# AD4DA-LightUI.net
KiCad netlist of a schematic drawn in EAGLE
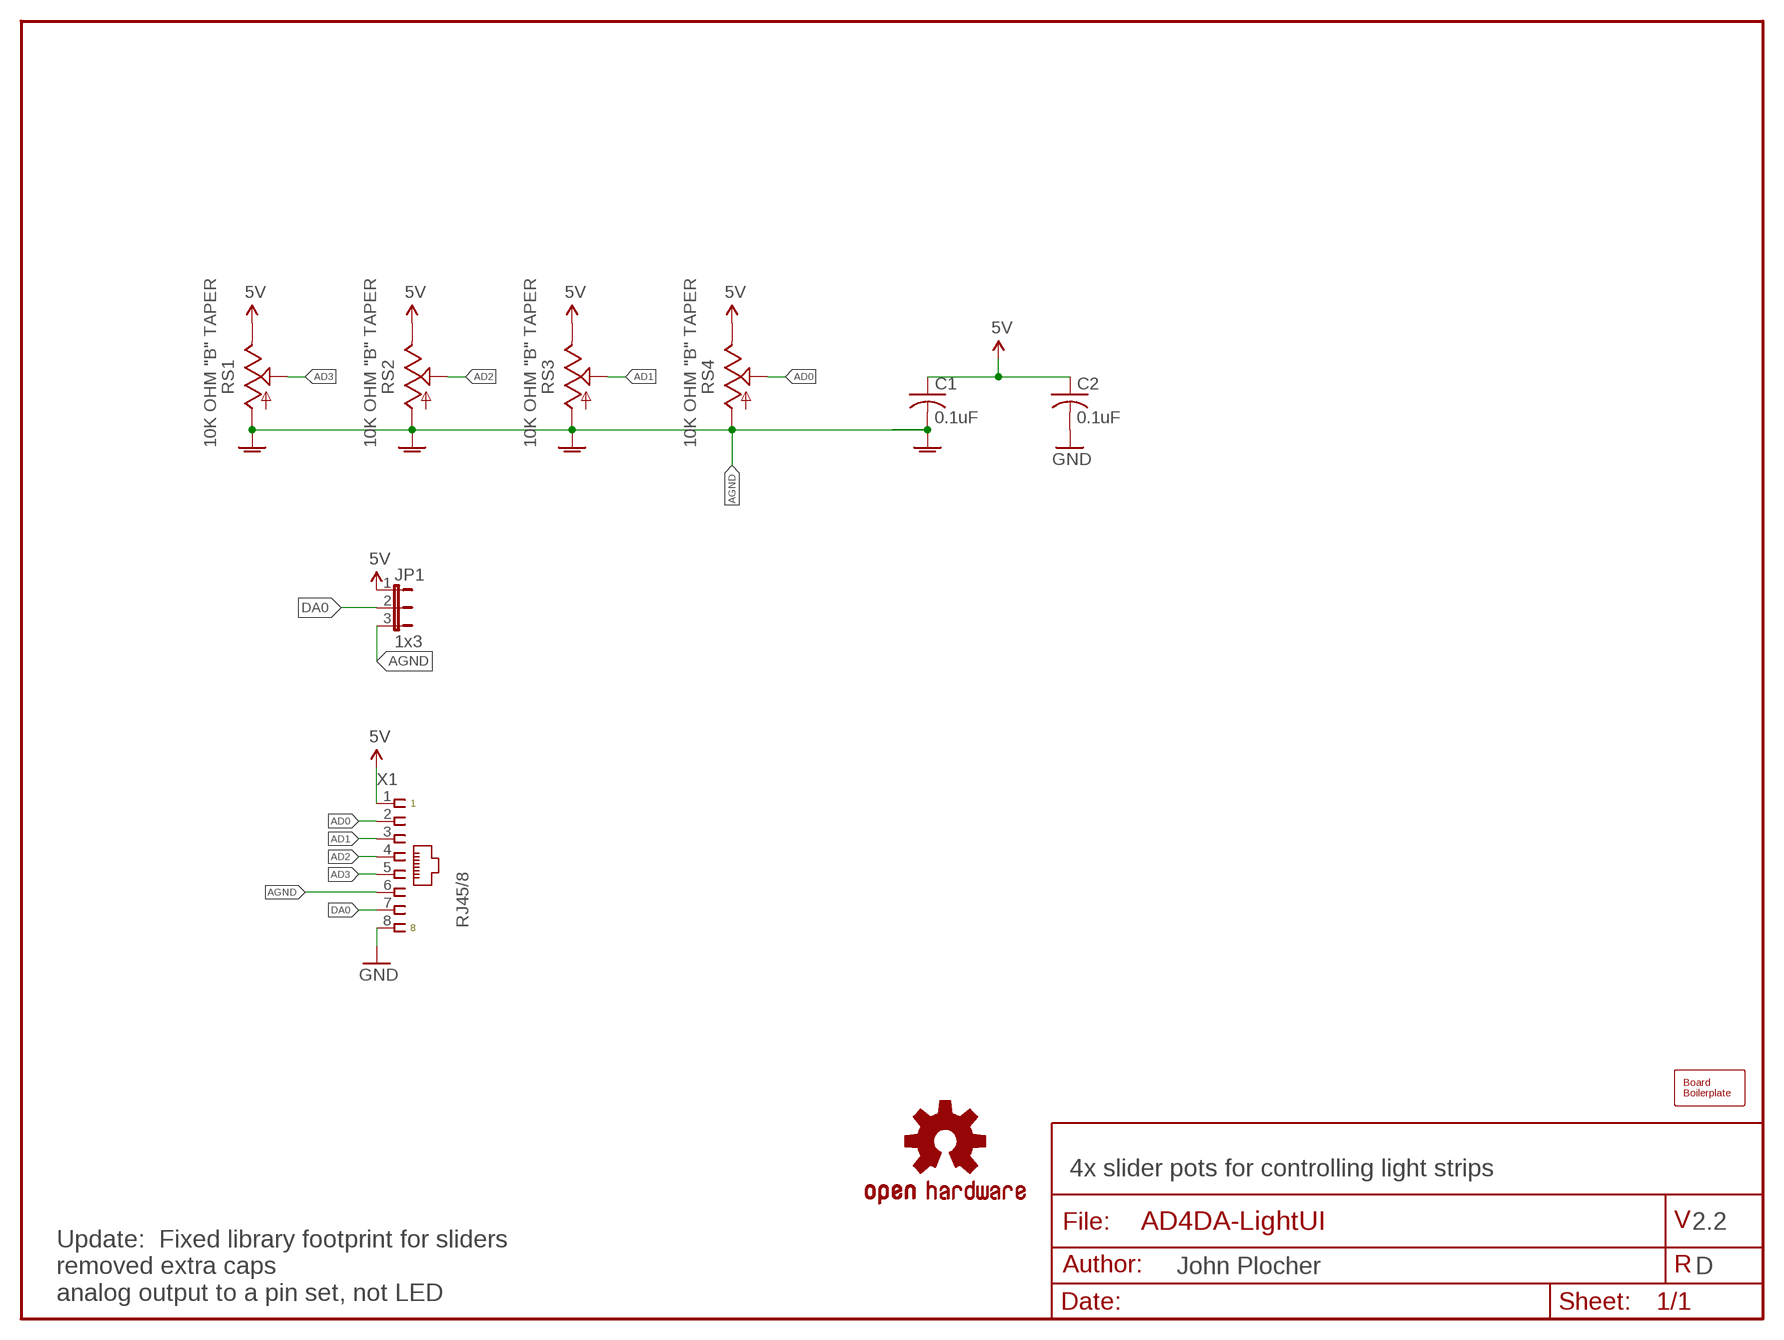
[diagram p0: schematic, sheet 1]

(export (version "E")
  (design (tool "Eeschema 10.0.6"))
  (components
    (comp (ref "BOARD1")
      (value "10x7cm")
      (footprint "eagle-import:BOARD-DINRAIL-3.17INX7CM")
      (libsource (lib "eagle-import") (part "BOARD80X70"))
    )
    (comp (ref "C1")
      (value "0.1uF")
      (footprint "eagle-import:C050-024X044")
      (libsource (lib "eagle-import") (part "CAPPTH1"))
    )
    (comp (ref "C2")
      (value "0.1uF")
      (footprint "eagle-import:C050-024X044")
      (libsource (lib "eagle-import") (part "CAPPTH1"))
    )
    (comp (ref "JP1")
      (value "1x3")
      (footprint "eagle-import:1X03")
      (libsource (lib "eagle-import") (part "JUMPER-3PTH-LOCK"))
    )
    (comp (ref "LOGO1")
      (value "DOC-OSHW-LOGO-L")
      (footprint "eagle-import:OSHW-LOGO-L")
      (libsource (lib "eagle-import") (part "DOC-OSHW-LOGO-L"))
    )
    (comp (ref "RS1")
      (value "10K OHM \"B\" TAPER")
      (footprint "eagle-import:SLIDER-45MM")
      (libsource (lib "eagle-import") (part "R-SLIDE-POT-45MM"))
    )
    (comp (ref "RS2")
      (value "10K OHM \"B\" TAPER")
      (footprint "eagle-import:SLIDER-45MM")
      (libsource (lib "eagle-import") (part "R-SLIDE-POT-45MM"))
    )
    (comp (ref "RS3")
      (value "10K OHM \"B\" TAPER")
      (footprint "eagle-import:SLIDER-45MM")
      (libsource (lib "eagle-import") (part "R-SLIDE-POT-45MM"))
    )
    (comp (ref "RS4")
      (value "10K OHM \"B\" TAPER")
      (footprint "eagle-import:SLIDER-45MM")
      (libsource (lib "eagle-import") (part "R-SLIDE-POT-45MM"))
    )
    (comp (ref "X1")
      (value "RJ45/8")
      (footprint "eagle-import:RJ45-NO-SHIELD")
      (libsource (lib "eagle-import") (part "CONNECTOR-RJ45-FRONT"))
    )
  )
  (nets
    (net (code "1") (name "5V") (class "Default")
      (node (ref "C1") (pin "1") (pinfunction "1_1") (pintype "passive"))
      (node (ref "C2") (pin "1") (pinfunction "1_1") (pintype "passive"))
      (node (ref "JP1") (pin "1") (pinfunction "1_1") (pintype "passive"))
      (node (ref "RS1") (pin "E") (pinfunction "E_E") (pintype "passive"))
      (node (ref "RS2") (pin "E") (pinfunction "E_E") (pintype "passive"))
      (node (ref "RS3") (pin "E") (pinfunction "E_E") (pintype "passive"))
      (node (ref "RS4") (pin "E") (pinfunction "E_E") (pintype "passive"))
      (node (ref "X1") (pin "1") (pinfunction "1_1") (pintype "passive"))
    )
    (net (code "2") (name "AD0") (class "Default")
      (node (ref "RS4") (pin "S") (pinfunction "S_S") (pintype "passive"))
      (node (ref "X1") (pin "2") (pinfunction "2_2") (pintype "passive"))
    )
    (net (code "3") (name "AD1") (class "Default")
      (node (ref "RS3") (pin "S") (pinfunction "S_S") (pintype "passive"))
      (node (ref "X1") (pin "3") (pinfunction "3_3") (pintype "passive"))
    )
    (net (code "4") (name "AD2") (class "Default")
      (node (ref "RS2") (pin "S") (pinfunction "S_S") (pintype "passive"))
      (node (ref "X1") (pin "4") (pinfunction "4_4") (pintype "passive"))
    )
    (net (code "5") (name "AD3") (class "Default")
      (node (ref "RS1") (pin "S") (pinfunction "S_S") (pintype "passive"))
      (node (ref "X1") (pin "5") (pinfunction "5_5") (pintype "passive"))
    )
    (net (code "6") (name "AGND") (class "Default")
      (node (ref "C1") (pin "2") (pinfunction "2_2") (pintype "passive"))
      (node (ref "JP1") (pin "3") (pinfunction "3_3") (pintype "passive"))
      (node (ref "RS1") (pin "A") (pinfunction "A_A") (pintype "passive"))
      (node (ref "RS1") (pin "AGND@0") (pinfunction "AGND_AGND@0") (pintype "power_in"))
      (node (ref "RS1") (pin "AGND@1") (pinfunction "AGND_AGND@1") (pintype "power_in"))
      (node (ref "RS2") (pin "A") (pinfunction "A_A") (pintype "passive"))
      (node (ref "RS2") (pin "AGND@0") (pinfunction "AGND_AGND@0") (pintype "power_in"))
      (node (ref "RS2") (pin "AGND@1") (pinfunction "AGND_AGND@1") (pintype "power_in"))
      (node (ref "RS3") (pin "A") (pinfunction "A_A") (pintype "passive"))
      (node (ref "RS3") (pin "AGND@0") (pinfunction "AGND_AGND@0") (pintype "power_in"))
      (node (ref "RS3") (pin "AGND@1") (pinfunction "AGND_AGND@1") (pintype "power_in"))
      (node (ref "RS4") (pin "A") (pinfunction "A_A") (pintype "passive"))
      (node (ref "RS4") (pin "AGND@0") (pinfunction "AGND_AGND@0") (pintype "power_in"))
      (node (ref "RS4") (pin "AGND@1") (pinfunction "AGND_AGND@1") (pintype "power_in"))
      (node (ref "X1") (pin "6") (pinfunction "6_6") (pintype "passive"))
    )
    (net (code "7") (name "DA0") (class "Default")
      (node (ref "JP1") (pin "2") (pinfunction "2_2") (pintype "passive"))
      (node (ref "X1") (pin "7") (pinfunction "7_7") (pintype "passive"))
    )
    (net (code "8") (name "GND") (class "Default")
      (node (ref "C2") (pin "2") (pinfunction "2_2") (pintype "passive"))
      (node (ref "X1") (pin "8") (pinfunction "8_8") (pintype "passive"))
    )
  )
)
